# simple-ldr.net
KiCad netlist of a schematic drawn in EAGLE
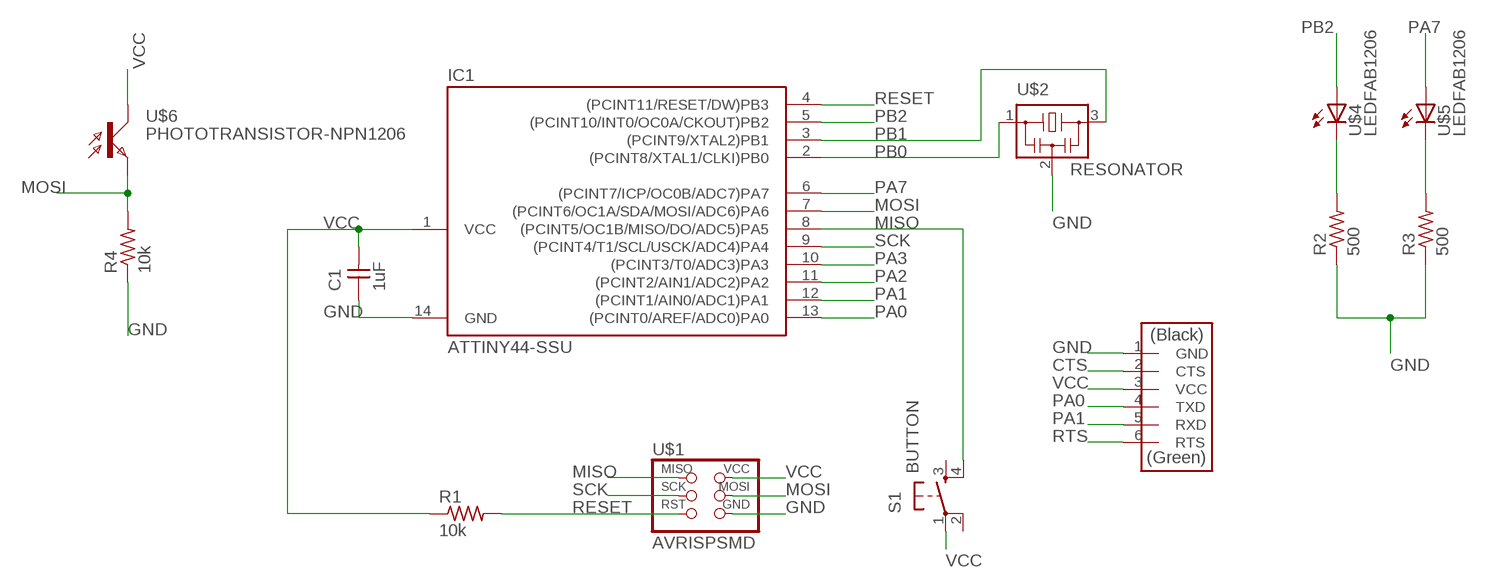
[diagram p0: schematic, sheet 1]

(export (version "E")
  (design (tool "Eeschema 10.0.6"))
  (components
    (comp (ref "C1")
      (value "1uF")
      (footprint "eagle-import:C1206FAB")
      (libsource (lib "eagle-import") (part "CAP-UNPOLARIZEDFAB"))
    )
    (comp (ref "IC1")
      (value "ATTINY44-SSU")
      (footprint "eagle-import:SOIC14")
      (libsource (lib "eagle-import") (part "ATTINY44-SSU"))
    )
    (comp (ref "R1")
      (value "10k")
      (footprint "eagle-import:R1206FAB")
      (libsource (lib "eagle-import") (part "RES-US1206FAB"))
    )
    (comp (ref "R2")
      (value "500")
      (footprint "eagle-import:R1206FAB")
      (libsource (lib "eagle-import") (part "RES-US1206FAB"))
    )
    (comp (ref "R3")
      (value "500")
      (footprint "eagle-import:R1206FAB")
      (libsource (lib "eagle-import") (part "RES-US1206FAB"))
    )
    (comp (ref "R4")
      (value "10k")
      (footprint "eagle-import:R1206FAB")
      (libsource (lib "eagle-import") (part "RES-US1206FAB"))
    )
    (comp (ref "S1")
      (value "BUTTON")
      (footprint "eagle-import:6MM_SWITCH")
      (libsource (lib "eagle-import") (part "6MM_SWITCH6MM_SWITCH"))
    )
    (comp (ref "U$1")
      (value "AVRISPSMD")
      (footprint "eagle-import:2X03SMD")
      (libsource (lib "eagle-import") (part "AVRISPSMD"))
    )
    (comp (ref "U$2")
      (value "RESONATOR")
      (footprint "eagle-import:EFOBM")
      (libsource (lib "eagle-import") (part "RESONATOR"))
    )
    (comp (ref "U$3")
      (value "FTDI-SMD-HEADER")
      (footprint "eagle-import:1X06SMD")
      (libsource (lib "eagle-import") (part "FTDI-SMD-HEADER"))
    )
    (comp (ref "U$4")
      (value "LEDFAB1206")
      (footprint "eagle-import:LED1206FAB")
      (libsource (lib "eagle-import") (part "LEDFAB1206"))
    )
    (comp (ref "U$5")
      (value "LEDFAB1206")
      (footprint "eagle-import:LED1206FAB")
      (libsource (lib "eagle-import") (part "LEDFAB1206"))
    )
    (comp (ref "U$6")
      (value "PHOTOTRANSISTOR-NPN1206")
      (footprint "eagle-import:OP1206")
      (libsource (lib "eagle-import") (part "PHOTOTRANSISTOR-NPN1206"))
    )
  )
  (nets
    (net (code "1") (name "/CTS") (class "Default")
      (node (ref "U$3") (pin "2") (pinfunction "CTS_2") (pintype "bidirectional"))
    )
    (net (code "2") (name "/GND") (class "Default")
      (node (ref "C1") (pin "1") (pinfunction "1_1") (pintype "passive"))
      (node (ref "IC1") (pin "14") (pinfunction "GND_14") (pintype "power_in"))
      (node (ref "R2") (pin "1") (pinfunction "1_1") (pintype "passive"))
      (node (ref "R3") (pin "1") (pinfunction "1_1") (pintype "passive"))
      (node (ref "R4") (pin "1") (pinfunction "1_1") (pintype "passive"))
      (node (ref "U$1") (pin "6") (pinfunction "GND_6") (pintype "passive"))
      (node (ref "U$2") (pin "2") (pinfunction "2_2") (pintype "passive"))
      (node (ref "U$3") (pin "1") (pinfunction "GND_1") (pintype "bidirectional"))
    )
    (net (code "3") (name "/MISO") (class "Default")
      (node (ref "IC1") (pin "8") (pinfunction "(PCINT5/OC1B/MISO/DO/ADC5)PA5_8") (pintype "bidirectional"))
      (node (ref "S1") (pin "4") (pinfunction "S1_4") (pintype "passive"))
      (node (ref "U$1") (pin "1") (pinfunction "MISO_1") (pintype "passive"))
    )
    (net (code "4") (name "/MOSI") (class "Default")
      (node (ref "IC1") (pin "7") (pinfunction "(PCINT6/OC1A/SDA/MOSI/ADC6)PA6_7") (pintype "bidirectional"))
      (node (ref "R4") (pin "2") (pinfunction "2_2") (pintype "passive"))
      (node (ref "U$1") (pin "4") (pinfunction "MOSI_4") (pintype "passive"))
      (node (ref "U$6") (pin "EMITTER") (pinfunction "E_EMITTER") (pintype "passive"))
    )
    (net (code "5") (name "/PA0") (class "Default")
      (node (ref "IC1") (pin "13") (pinfunction "(PCINT0/AREF/ADC0)PA0_13") (pintype "bidirectional"))
      (node (ref "U$3") (pin "4") (pinfunction "TXD_4") (pintype "bidirectional"))
    )
    (net (code "6") (name "/PA1") (class "Default")
      (node (ref "IC1") (pin "12") (pinfunction "(PCINT1/AIN0/ADC1)PA1_12") (pintype "bidirectional"))
      (node (ref "U$3") (pin "5") (pinfunction "RXD_5") (pintype "bidirectional"))
    )
    (net (code "7") (name "/PA2") (class "Default")
      (node (ref "IC1") (pin "11") (pinfunction "(PCINT2/AIN1/ADC2)PA2_11") (pintype "bidirectional"))
    )
    (net (code "8") (name "/PA3") (class "Default")
      (node (ref "IC1") (pin "10") (pinfunction "(PCINT3/T0/ADC3)PA3_10") (pintype "bidirectional"))
    )
    (net (code "9") (name "/PA7") (class "Default")
      (node (ref "IC1") (pin "6") (pinfunction "(PCINT7/ICP/OC0B/ADC7)PA7_6") (pintype "bidirectional"))
      (node (ref "U$5") (pin "1") (pinfunction "A_1") (pintype "passive"))
    )
    (net (code "10") (name "/PB0") (class "Default")
      (node (ref "IC1") (pin "2") (pinfunction "(PCINT8/XTAL1/CLKI)PB0_2") (pintype "bidirectional"))
      (node (ref "U$2") (pin "1") (pinfunction "1_1") (pintype "passive"))
    )
    (net (code "11") (name "/PB1") (class "Default")
      (node (ref "IC1") (pin "3") (pinfunction "(PCINT9/XTAL2)PB1_3") (pintype "bidirectional"))
      (node (ref "U$2") (pin "3") (pinfunction "3_3") (pintype "passive"))
    )
    (net (code "12") (name "/PB2") (class "Default")
      (node (ref "IC1") (pin "5") (pinfunction "(PCINT10/INT0/OC0A/CKOUT)PB2_5") (pintype "bidirectional"))
      (node (ref "U$4") (pin "1") (pinfunction "A_1") (pintype "passive"))
    )
    (net (code "13") (name "/RESET") (class "Default")
      (node (ref "IC1") (pin "4") (pinfunction "(PCINT11/RESET/DW)PB3_4") (pintype "bidirectional"))
      (node (ref "R1") (pin "2") (pinfunction "2_2") (pintype "passive"))
      (node (ref "U$1") (pin "5") (pinfunction "RST_5") (pintype "passive"))
    )
    (net (code "14") (name "/RTS") (class "Default")
      (node (ref "U$3") (pin "6") (pinfunction "RTS_6") (pintype "bidirectional"))
    )
    (net (code "15") (name "/SCK") (class "Default")
      (node (ref "IC1") (pin "9") (pinfunction "(PCINT4/T1/SCL/USCK/ADC4)PA4_9") (pintype "bidirectional"))
      (node (ref "U$1") (pin "3") (pinfunction "SCK_3") (pintype "passive"))
    )
    (net (code "16") (name "/VCC") (class "Default")
      (node (ref "C1") (pin "2") (pinfunction "2_2") (pintype "passive"))
      (node (ref "IC1") (pin "1") (pinfunction "VCC_1") (pintype "power_in"))
      (node (ref "R1") (pin "1") (pinfunction "1_1") (pintype "passive"))
      (node (ref "S1") (pin "1") (pinfunction "P_1") (pintype "passive"))
      (node (ref "U$1") (pin "2") (pinfunction "VCC_2") (pintype "passive"))
      (node (ref "U$3") (pin "3") (pinfunction "VCC_3") (pintype "bidirectional"))
      (node (ref "U$6") (pin "COLLECTOR") (pinfunction "C_COLLECTOR") (pintype "passive"))
    )
    (net (code "17") (name "Net-(U$4-C)") (class "Default")
      (node (ref "R2") (pin "2") (pinfunction "2_2") (pintype "passive"))
      (node (ref "U$4") (pin "2") (pinfunction "C_2") (pintype "passive"))
    )
    (net (code "18") (name "Net-(U$5-C)") (class "Default")
      (node (ref "R3") (pin "2") (pinfunction "2_2") (pintype "passive"))
      (node (ref "U$5") (pin "2") (pinfunction "C_2") (pintype "passive"))
    )
    (net (code "19") (name "unconnected-(S1-P1-Pad2)") (class "Default")
      (node (ref "S1") (pin "2") (pinfunction "P1_2") (pintype "passive"))
    )
    (net (code "20") (name "unconnected-(S1-S-Pad3)") (class "Default")
      (node (ref "S1") (pin "3") (pinfunction "S_3") (pintype "passive"))
    )
  )
)
